# Sunboost.net
KiCad netlist of a schematic drawn in Altium Designer
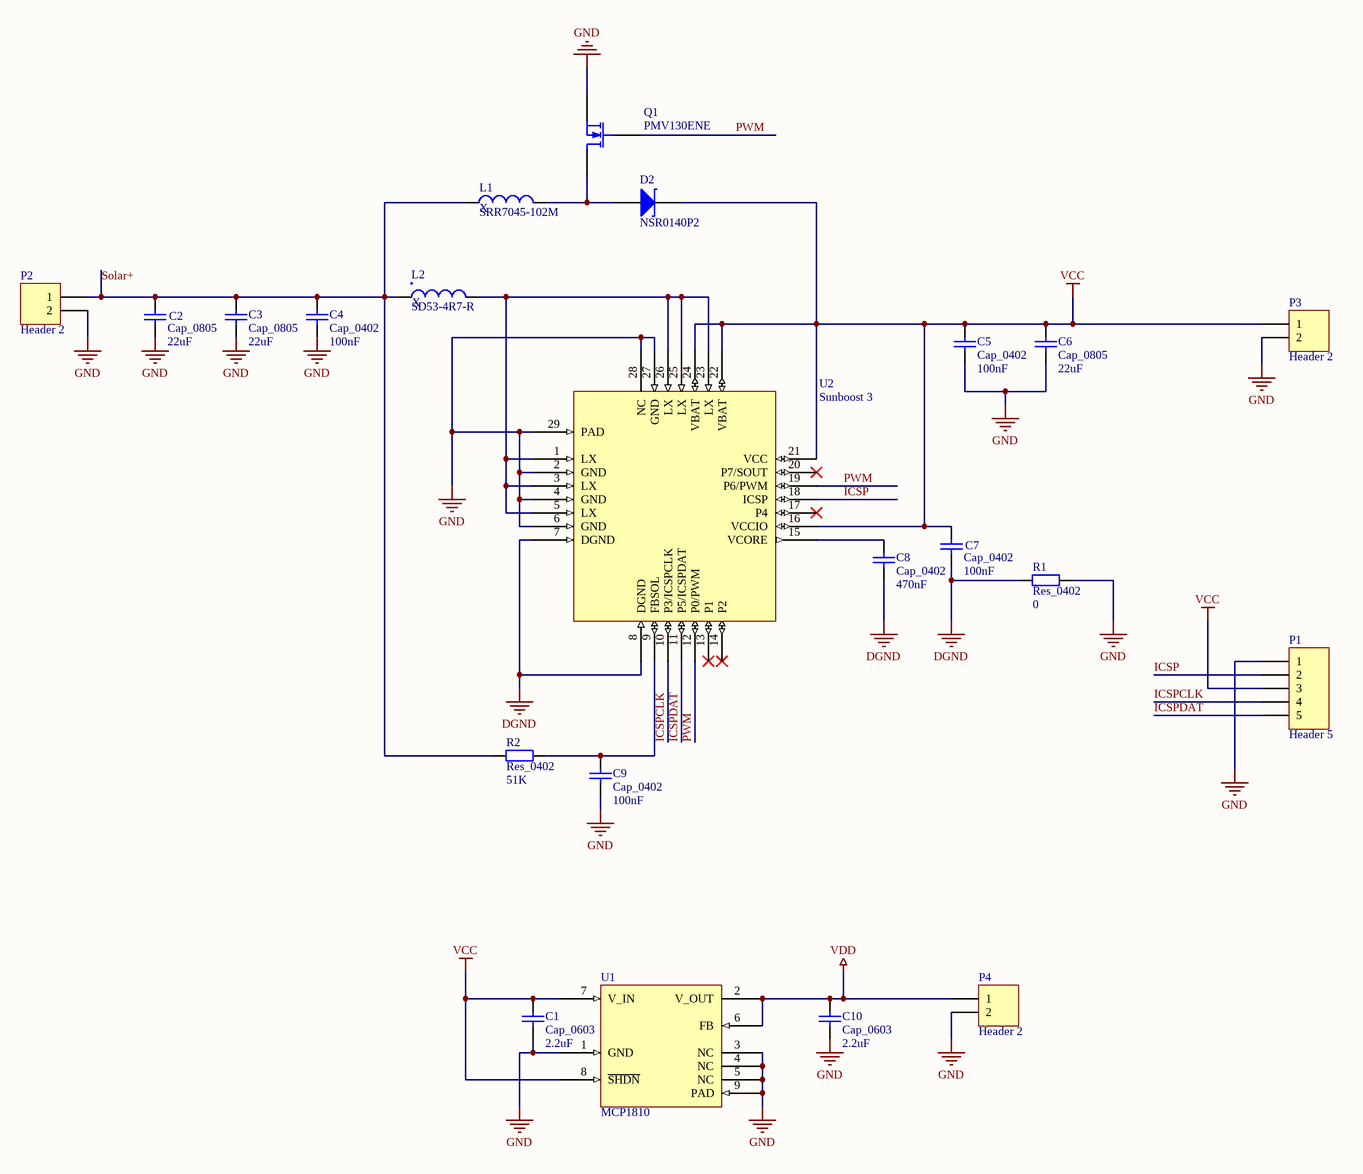
[diagram p0: Sunboost.SchDoc]

(export (version "E")
  (design (tool "Eeschema 10.0.6"))
  (components
    (comp (ref "C1")
      (value "Cap_0603")
      (footprint "0603")
      (description "Capacitor")
      (fields (field (name "ALTIUM_VALUE") "2.2uF") (field (name "PUBLISHER") "Altium Limited"))
      (libsource (lib "Schematic_Components") (part "Cap_0603"))
    )
    (comp (ref "C2")
      (value "Cap_0805")
      (footprint "0805")
      (description "Capacitor")
      (fields (field (name "ALTIUM_VALUE") "22uF") (field (name "PUBLISHER") "Altium Limited"))
      (libsource (lib "Schematic_Components") (part "Cap_0805"))
    )
    (comp (ref "C3")
      (value "Cap_0805")
      (footprint "0805")
      (description "Capacitor")
      (fields (field (name "ALTIUM_VALUE") "22uF") (field (name "PUBLISHER") "Altium Limited"))
      (libsource (lib "Schematic_Components") (part "Cap_0805"))
    )
    (comp (ref "C4")
      (value "Cap_0402")
      (footprint "0402")
      (description "Capacitor")
      (fields (field (name "ALTIUM_VALUE") "100nF") (field (name "PUBLISHER") "Altium Limited"))
      (libsource (lib "Schematic_Components") (part "Cap_0402"))
    )
    (comp (ref "C5")
      (value "Cap_0402")
      (footprint "0402")
      (description "Capacitor")
      (fields (field (name "ALTIUM_VALUE") "100nF") (field (name "PUBLISHER") "Altium Limited"))
      (libsource (lib "Schematic_Components") (part "Cap_0402"))
    )
    (comp (ref "C6")
      (value "Cap_0805")
      (footprint "0805")
      (description "Capacitor")
      (fields (field (name "ALTIUM_VALUE") "22uF") (field (name "PUBLISHER") "Altium Limited"))
      (libsource (lib "Schematic_Components") (part "Cap_0805"))
    )
    (comp (ref "C7")
      (value "Cap_0402")
      (footprint "0402")
      (description "Capacitor")
      (fields (field (name "ALTIUM_VALUE") "100nF") (field (name "PUBLISHER") "Altium Limited"))
      (libsource (lib "Schematic_Components") (part "Cap_0402"))
    )
    (comp (ref "C8")
      (value "Cap_0402")
      (footprint "0402")
      (description "Capacitor")
      (fields (field (name "ALTIUM_VALUE") "470nF") (field (name "PUBLISHER") "Altium Limited"))
      (libsource (lib "Schematic_Components") (part "Cap_0402"))
    )
    (comp (ref "C9")
      (value "Cap_0402")
      (footprint "0402")
      (description "Capacitor")
      (fields (field (name "ALTIUM_VALUE") "100nF") (field (name "PUBLISHER") "Altium Limited"))
      (libsource (lib "Schematic_Components") (part "Cap_0402"))
    )
    (comp (ref "C10")
      (value "Cap_0603")
      (footprint "0603")
      (description "Capacitor")
      (fields (field (name "ALTIUM_VALUE") "2.2uF") (field (name "PUBLISHER") "Altium Limited"))
      (libsource (lib "Schematic_Components") (part "Cap_0603"))
    )
    (comp (ref "D2")
      (value "NSR0140P2")
      (footprint "SOD-923")
      (description "Typical INFRARED GaAs LED")
      (fields (field (name "PUBLISHER") "Altium Limited"))
      (libsource (lib "Schematic_Components") (part "NSR0140P2"))
    )
    (comp (ref "L1")
      (value "SRR7045-102M")
      (footprint "SRR7045-102M")
      (description "Inductor")
      (fields (field (name "ALTIUM_VALUE") "X"))
      (libsource (lib "Schematic_Components") (part "SRR7045-102M"))
    )
    (comp (ref "L2")
      (value "SD53-4R7-R")
      (footprint "SD53-4R7-R")
      (description "Inductor")
      (fields (field (name "ALTIUM_VALUE") "X"))
      (libsource (lib "Schematic_Components") (part "SD53-4R7-R"))
    )
    (comp (ref "P1")
      (value "Header 5")
      (footprint "HDR1X5")
      (description "Header, 5-Pin")
      (fields (field (name "PUBLISHER") "Altium Limited"))
      (libsource (lib "Miscellaneous Connectors") (part "Header 5"))
    )
    (comp (ref "P2")
      (value "Header 2")
      (footprint "HDR1X2")
      (description "Header, 2-Pin")
      (fields (field (name "PUBLISHER") "Altium Limited"))
      (libsource (lib "Miscellaneous Connectors") (part "Header 2"))
    )
    (comp (ref "P3")
      (value "Header 2")
      (footprint "HDR1X2")
      (description "Header, 2-Pin")
      (fields (field (name "PUBLISHER") "Altium Limited"))
      (libsource (lib "") (part "Header 2_1"))
    )
    (comp (ref "P4")
      (value "Header 2")
      (footprint "HDR1X2")
      (description "Header, 2-Pin")
      (fields (field (name "PUBLISHER") "Altium Limited"))
      (libsource (lib "") (part "Header 2_1"))
    )
    (comp (ref "Q1")
      (value "PMV130ENE")
      (footprint "SOT-23")
      (description "N-Channel MOSFET")
      (fields (field (name "PUBLISHER") "Altium Limited"))
      (libsource (lib "Schematic_Components") (part "PMV130ENE"))
    )
    (comp (ref "R1")
      (value "Res_0402")
      (footprint "0402")
      (description "Resistor")
      (fields (field (name "ALTIUM_VALUE") "0") (field (name "PUBLISHER") "Altium Limited"))
      (libsource (lib "Schematic_Components") (part "Res_0402"))
    )
    (comp (ref "R2")
      (value "Res_0402")
      (footprint "0402")
      (description "Resistor")
      (fields (field (name "ALTIUM_VALUE") "51K") (field (name "PUBLISHER") "Altium Limited"))
      (libsource (lib "Schematic_Components") (part "Res_0402"))
    )
    (comp (ref "U1")
      (value "MCP1810")
      (footprint "VDFN8")
      (description "3V Regulator, 150 mA")
      (libsource (lib "Schematic_Components") (part "MCP1810"))
    )
    (comp (ref "U2")
      (value "Sunboost 3")
      (footprint "28-QFN_0.4mm")
      (description "Initvation Sunboost 3")
      (libsource (lib "Schematic_Components") (part "Sunboost 3"))
    )
  )
  (nets
    (net (code "1") (name "/ICSP") (class "Default")
      (node (ref "P1") (pin "2") (pinfunction "2_2") (pintype "passive"))
      (node (ref "U2") (pin "18") (pinfunction "ICSP_18") (pintype "bidirectional"))
    )
    (net (code "2") (name "/ICSPCLK") (class "Default")
      (node (ref "P1") (pin "4") (pinfunction "4_4") (pintype "passive"))
      (node (ref "U2") (pin "10") (pinfunction "P3/ICSPCLK_10") (pintype "bidirectional"))
    )
    (net (code "3") (name "/ICSPDAT") (class "Default")
      (node (ref "P1") (pin "5") (pinfunction "5_5") (pintype "passive"))
      (node (ref "U2") (pin "11") (pinfunction "P5/ICSPDAT_11") (pintype "bidirectional"))
    )
    (net (code "4") (name "/PWM") (class "Default")
      (node (ref "Q1") (pin "1") (pinfunction "G_1") (pintype "passive"))
      (node (ref "U2") (pin "12") (pinfunction "P0/PWM_12") (pintype "bidirectional"))
      (node (ref "U2") (pin "19") (pinfunction "P6/PWM_19") (pintype "bidirectional"))
    )
    (net (code "5") (name "/Solar+") (class "Default")
      (node (ref "C2") (pin "2") (pinfunction "2_2") (pintype "passive"))
      (node (ref "C3") (pin "2") (pinfunction "2_2") (pintype "passive"))
      (node (ref "C4") (pin "2") (pinfunction "2_2") (pintype "passive"))
      (node (ref "L1") (pin "1") (pinfunction "1_1") (pintype "passive"))
      (node (ref "L2") (pin "1") (pinfunction "1_1") (pintype "passive"))
      (node (ref "P2") (pin "1") (pinfunction "1_1") (pintype "passive"))
      (node (ref "R2") (pin "1") (pinfunction "1_1") (pintype "passive"))
    )
    (net (code "6") (name "DGND") (class "Default")
      (node (ref "C7") (pin "1") (pinfunction "1_1") (pintype "passive"))
      (node (ref "C8") (pin "1") (pinfunction "1_1") (pintype "passive"))
      (node (ref "R1") (pin "1") (pinfunction "1_1") (pintype "passive"))
      (node (ref "U2") (pin "7") (pinfunction "DGND_7") (pintype "input"))
      (node (ref "U2") (pin "8") (pinfunction "DGND_8") (pintype "input"))
    )
    (net (code "7") (name "GND") (class "Default")
      (node (ref "C1") (pin "1") (pinfunction "1_1") (pintype "passive"))
      (node (ref "C10") (pin "1") (pinfunction "1_1") (pintype "passive"))
      (node (ref "C2") (pin "1") (pinfunction "1_1") (pintype "passive"))
      (node (ref "C3") (pin "1") (pinfunction "1_1") (pintype "passive"))
      (node (ref "C4") (pin "1") (pinfunction "1_1") (pintype "passive"))
      (node (ref "C5") (pin "1") (pinfunction "1_1") (pintype "passive"))
      (node (ref "C6") (pin "1") (pinfunction "1_1") (pintype "passive"))
      (node (ref "C9") (pin "1") (pinfunction "1_1") (pintype "passive"))
      (node (ref "P1") (pin "1") (pinfunction "1_1") (pintype "passive"))
      (node (ref "P2") (pin "2") (pinfunction "2_2") (pintype "passive"))
      (node (ref "P3") (pin "2") (pinfunction "2_2") (pintype "passive"))
      (node (ref "P4") (pin "2") (pinfunction "2_2") (pintype "passive"))
      (node (ref "Q1") (pin "2") (pinfunction "S_2") (pintype "passive"))
      (node (ref "R1") (pin "2") (pinfunction "2_2") (pintype "passive"))
      (node (ref "U1") (pin "1") (pinfunction "GND_1") (pintype "input"))
      (node (ref "U1") (pin "3") (pinfunction "NC_3") (pintype "passive"))
      (node (ref "U1") (pin "4") (pinfunction "NC_4") (pintype "passive"))
      (node (ref "U1") (pin "5") (pinfunction "NC_5") (pintype "passive"))
      (node (ref "U1") (pin "9") (pinfunction "PAD_9") (pintype "input"))
      (node (ref "U2") (pin "2") (pinfunction "GND_2") (pintype "input"))
      (node (ref "U2") (pin "27") (pinfunction "GND_27") (pintype "input"))
      (node (ref "U2") (pin "28") (pinfunction "NC_28") (pintype "passive"))
      (node (ref "U2") (pin "29") (pinfunction "PAD_29") (pintype "input"))
      (node (ref "U2") (pin "4") (pinfunction "GND_4") (pintype "input"))
      (node (ref "U2") (pin "6") (pinfunction "GND_6") (pintype "input"))
    )
    (net (code "8") (name "Net-(D2-A)") (class "Default")
      (node (ref "D2") (pin "2") (pinfunction "A_2") (pintype "passive"))
      (node (ref "L1") (pin "2") (pinfunction "2_2") (pintype "passive"))
      (node (ref "Q1") (pin "3") (pinfunction "D_3") (pintype "passive"))
    )
    (net (code "9") (name "Net-(L2-Pad2)") (class "Default")
      (node (ref "L2") (pin "2") (pinfunction "2_2") (pintype "passive"))
      (node (ref "U2") (pin "1") (pinfunction "LX_1") (pintype "input"))
      (node (ref "U2") (pin "23") (pinfunction "LX_23") (pintype "input"))
      (node (ref "U2") (pin "25") (pinfunction "LX_25") (pintype "input"))
      (node (ref "U2") (pin "26") (pinfunction "LX_26") (pintype "input"))
      (node (ref "U2") (pin "3") (pinfunction "LX_3") (pintype "input"))
      (node (ref "U2") (pin "5") (pinfunction "LX_5") (pintype "input"))
    )
    (net (code "10") (name "Net-(U2-FBSOL)") (class "Default")
      (node (ref "C9") (pin "2") (pinfunction "2_2") (pintype "passive"))
      (node (ref "R2") (pin "2") (pinfunction "2_2") (pintype "passive"))
      (node (ref "U2") (pin "9") (pinfunction "FBSOL_9") (pintype "bidirectional"))
    )
    (net (code "11") (name "Net-(U2-VCORE)") (class "Default")
      (node (ref "C8") (pin "2") (pinfunction "2_2") (pintype "passive"))
      (node (ref "U2") (pin "15") (pinfunction "VCORE_15") (pintype "output"))
    )
    (net (code "12") (name "VCC") (class "Default")
      (node (ref "C1") (pin "2") (pinfunction "2_2") (pintype "passive"))
      (node (ref "C5") (pin "2") (pinfunction "2_2") (pintype "passive"))
      (node (ref "C6") (pin "2") (pinfunction "2_2") (pintype "passive"))
      (node (ref "C7") (pin "2") (pinfunction "2_2") (pintype "passive"))
      (node (ref "D2") (pin "1") (pinfunction "K_1") (pintype "passive"))
      (node (ref "P1") (pin "3") (pinfunction "3_3") (pintype "passive"))
      (node (ref "P3") (pin "1") (pinfunction "1_1") (pintype "passive"))
      (node (ref "U1") (pin "7") (pinfunction "V_IN_7") (pintype "input"))
      (node (ref "U1") (pin "8") (pinfunction "~{SHDN}_8") (pintype "input"))
      (node (ref "U2") (pin "16") (pinfunction "VCCIO_16") (pintype "bidirectional"))
      (node (ref "U2") (pin "21") (pinfunction "VCC_21") (pintype "bidirectional"))
      (node (ref "U2") (pin "22") (pinfunction "VBAT_22") (pintype "bidirectional"))
      (node (ref "U2") (pin "24") (pinfunction "VBAT_24") (pintype "bidirectional"))
    )
    (net (code "13") (name "VDD") (class "Default")
      (node (ref "C10") (pin "2") (pinfunction "2_2") (pintype "passive"))
      (node (ref "P4") (pin "1") (pinfunction "1_1") (pintype "passive"))
      (node (ref "U1") (pin "2") (pinfunction "V_OUT_2") (pintype "passive"))
      (node (ref "U1") (pin "6") (pinfunction "FB_6") (pintype "input"))
    )
    (net (code "14") (name "unconnected-(U2-P1-Pad13)") (class "Default")
      (node (ref "U2") (pin "13") (pinfunction "P1_13") (pintype "bidirectional+no_connect"))
    )
    (net (code "15") (name "unconnected-(U2-P2-Pad14)") (class "Default")
      (node (ref "U2") (pin "14") (pinfunction "P2_14") (pintype "bidirectional+no_connect"))
    )
    (net (code "16") (name "unconnected-(U2-P4-Pad17)") (class "Default")
      (node (ref "U2") (pin "17") (pinfunction "P4_17") (pintype "bidirectional+no_connect"))
    )
    (net (code "17") (name "unconnected-(U2-P7{slash}SOUT-Pad20)") (class "Default")
      (node (ref "U2") (pin "20") (pinfunction "P7/SOUT_20") (pintype "bidirectional+no_connect"))
    )
  )
)
